# SCH_hacker-card_2024-09-15.net
KiCad netlist of a schematic drawn in EasyEDA
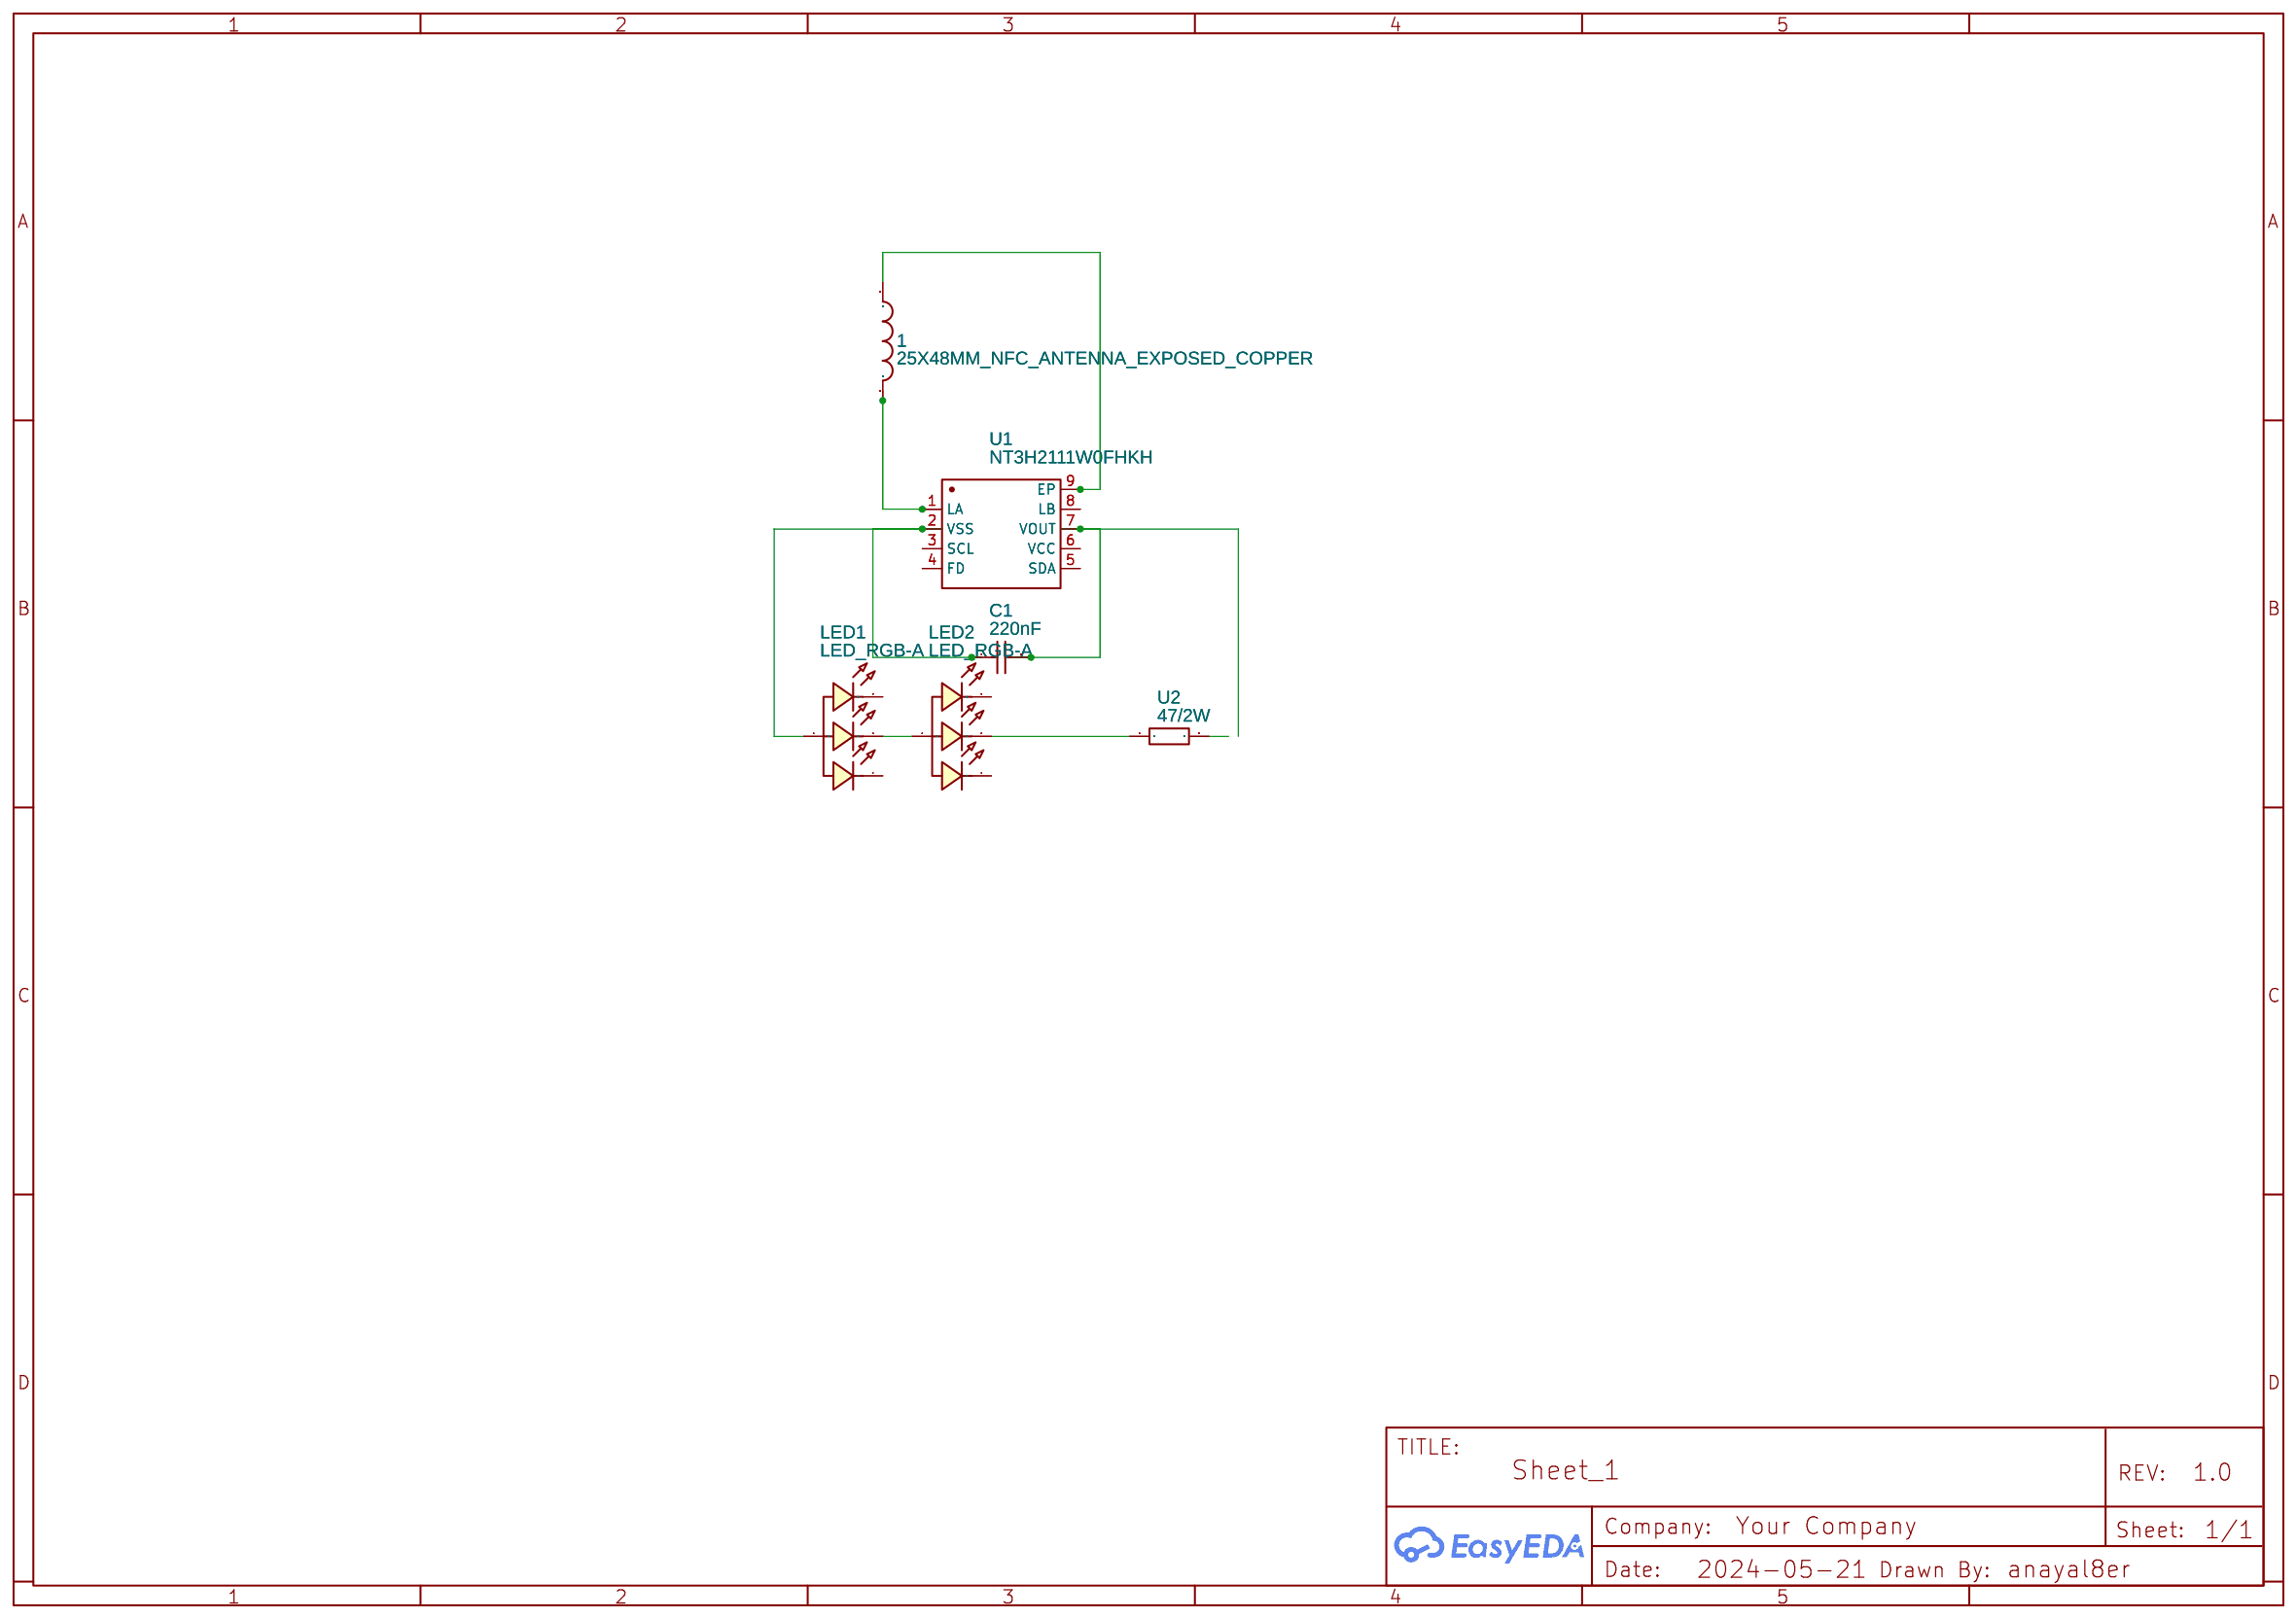
[diagram p0: schematic sheet]

(export (version "E")
  (design (tool "Eeschema 10.0.6"))
  (components
    (comp (ref "1")
      (value "25X48MM_NFC_ANTENNA_EXPOSED_COPPER")
      (libsource (lib "") (part "25X48MM_NFC_ANTENNA_EXPOSED_COPPER"))
    )
    (comp (ref "C1")
      (value "220nF")
      (fields
        (field (name "Manufacturer Part") "CL21B224KBFNNNE")
        (field (name "Manufacturer") "SAMSUNG(三星)")
      )
      (libsource (lib "") (part "CL21B224KBFNNNE"))
    )
    (comp (ref "LED1")
      (value "LED_RGB-A")
      (fields (field (name "Manufacturer Part") "LED_RGB红蓝双色"))
      (libsource (lib "") (part "LED_RGB-A"))
    )
    (comp (ref "LED2")
      (value "LED_RGB-A")
      (fields (field (name "Manufacturer Part") "LED_RGB红蓝双色"))
      (libsource (lib "") (part "LED_RGB-A"))
    )
    (comp (ref "U1")
      (value "NT3H2111W0FHKH")
      (fields (field (name "Manufacturer") "NXP(恩智浦)"))
      (libsource (lib "") (part "NT3H2111W0FHKH"))
    )
    (comp (ref "U2") (value "47/2W") (libsource (lib "") (part "47/2W")))
  )
  (nets
    (net (code "1") (name "Net-(LED1-Pad2)") (class "Default")
      (node (ref "LED1") (pin "2") (pinfunction "2_2") (pintype "unspecified"))
      (node (ref "LED2") (pin "1") (pinfunction "1_1") (pintype "unspecified"))
    )
    (net (code "2") (name "Net-(LED2-Pad2)") (class "Default")
      (node (ref "LED2") (pin "2") (pinfunction "2_2") (pintype "unspecified"))
      (node (ref "U2") (pin "1") (pinfunction "1_1") (pintype "unspecified"))
    )
    (net (code "3") (name "Net-(U1-EP)") (class "Default")
      (node (ref "1") (pin "P$1") (pinfunction "P$1_P$1") (pintype "bidirectional"))
      (node (ref "U1") (pin "9") (pinfunction "EP_9") (pintype "unspecified"))
    )
    (net (code "4") (name "Net-(U1-LA)") (class "Default")
      (node (ref "1") (pin "P$2") (pinfunction "P$2_P$2") (pintype "bidirectional"))
      (node (ref "U1") (pin "1") (pinfunction "LA_1") (pintype "unspecified"))
    )
    (net (code "5") (name "Net-(U1-VOUT)") (class "Default")
      (node (ref "C1") (pin "2") (pinfunction "2_2") (pintype "input"))
      (node (ref "U1") (pin "7") (pinfunction "VOUT_7") (pintype "unspecified"))
    )
    (net (code "6") (name "Net-(U1-VSS)") (class "Default")
      (node (ref "C1") (pin "1") (pinfunction "1_1") (pintype "input"))
      (node (ref "LED1") (pin "1") (pinfunction "1_1") (pintype "unspecified"))
      (node (ref "U1") (pin "2") (pinfunction "VSS_2") (pintype "unspecified"))
    )
    (net (code "7") (name "unconnected-(LED1-Pad3)") (class "Default")
      (node (ref "LED1") (pin "3") (pinfunction "3_3") (pintype "unspecified"))
    )
    (net (code "8") (name "unconnected-(LED1-Pad4)") (class "Default")
      (node (ref "LED1") (pin "4") (pinfunction "4_4") (pintype "unspecified"))
    )
    (net (code "9") (name "unconnected-(LED2-Pad3)") (class "Default")
      (node (ref "LED2") (pin "3") (pinfunction "3_3") (pintype "unspecified"))
    )
    (net (code "10") (name "unconnected-(LED2-Pad4)") (class "Default")
      (node (ref "LED2") (pin "4") (pinfunction "4_4") (pintype "unspecified"))
    )
    (net (code "11") (name "unconnected-(U1-FD-Pad4)") (class "Default")
      (node (ref "U1") (pin "4") (pinfunction "FD_4") (pintype "unspecified"))
    )
    (net (code "12") (name "unconnected-(U1-LB-Pad8)") (class "Default")
      (node (ref "U1") (pin "8") (pinfunction "LB_8") (pintype "unspecified"))
    )
    (net (code "13") (name "unconnected-(U1-SCL-Pad3)") (class "Default")
      (node (ref "U1") (pin "3") (pinfunction "SCL_3") (pintype "unspecified"))
    )
    (net (code "14") (name "unconnected-(U1-SDA-Pad5)") (class "Default")
      (node (ref "U1") (pin "5") (pinfunction "SDA_5") (pintype "unspecified"))
    )
    (net (code "15") (name "unconnected-(U1-VCC-Pad6)") (class "Default")
      (node (ref "U1") (pin "6") (pinfunction "VCC_6") (pintype "unspecified"))
    )
    (net (code "16") (name "unconnected-(U2-Pad2)") (class "Default")
      (node (ref "U2") (pin "2") (pinfunction "2_2") (pintype "unspecified"))
    )
  )
)
